# ATmega_2560_Pro.net
KiCad netlist of a schematic drawn in Altium Designer
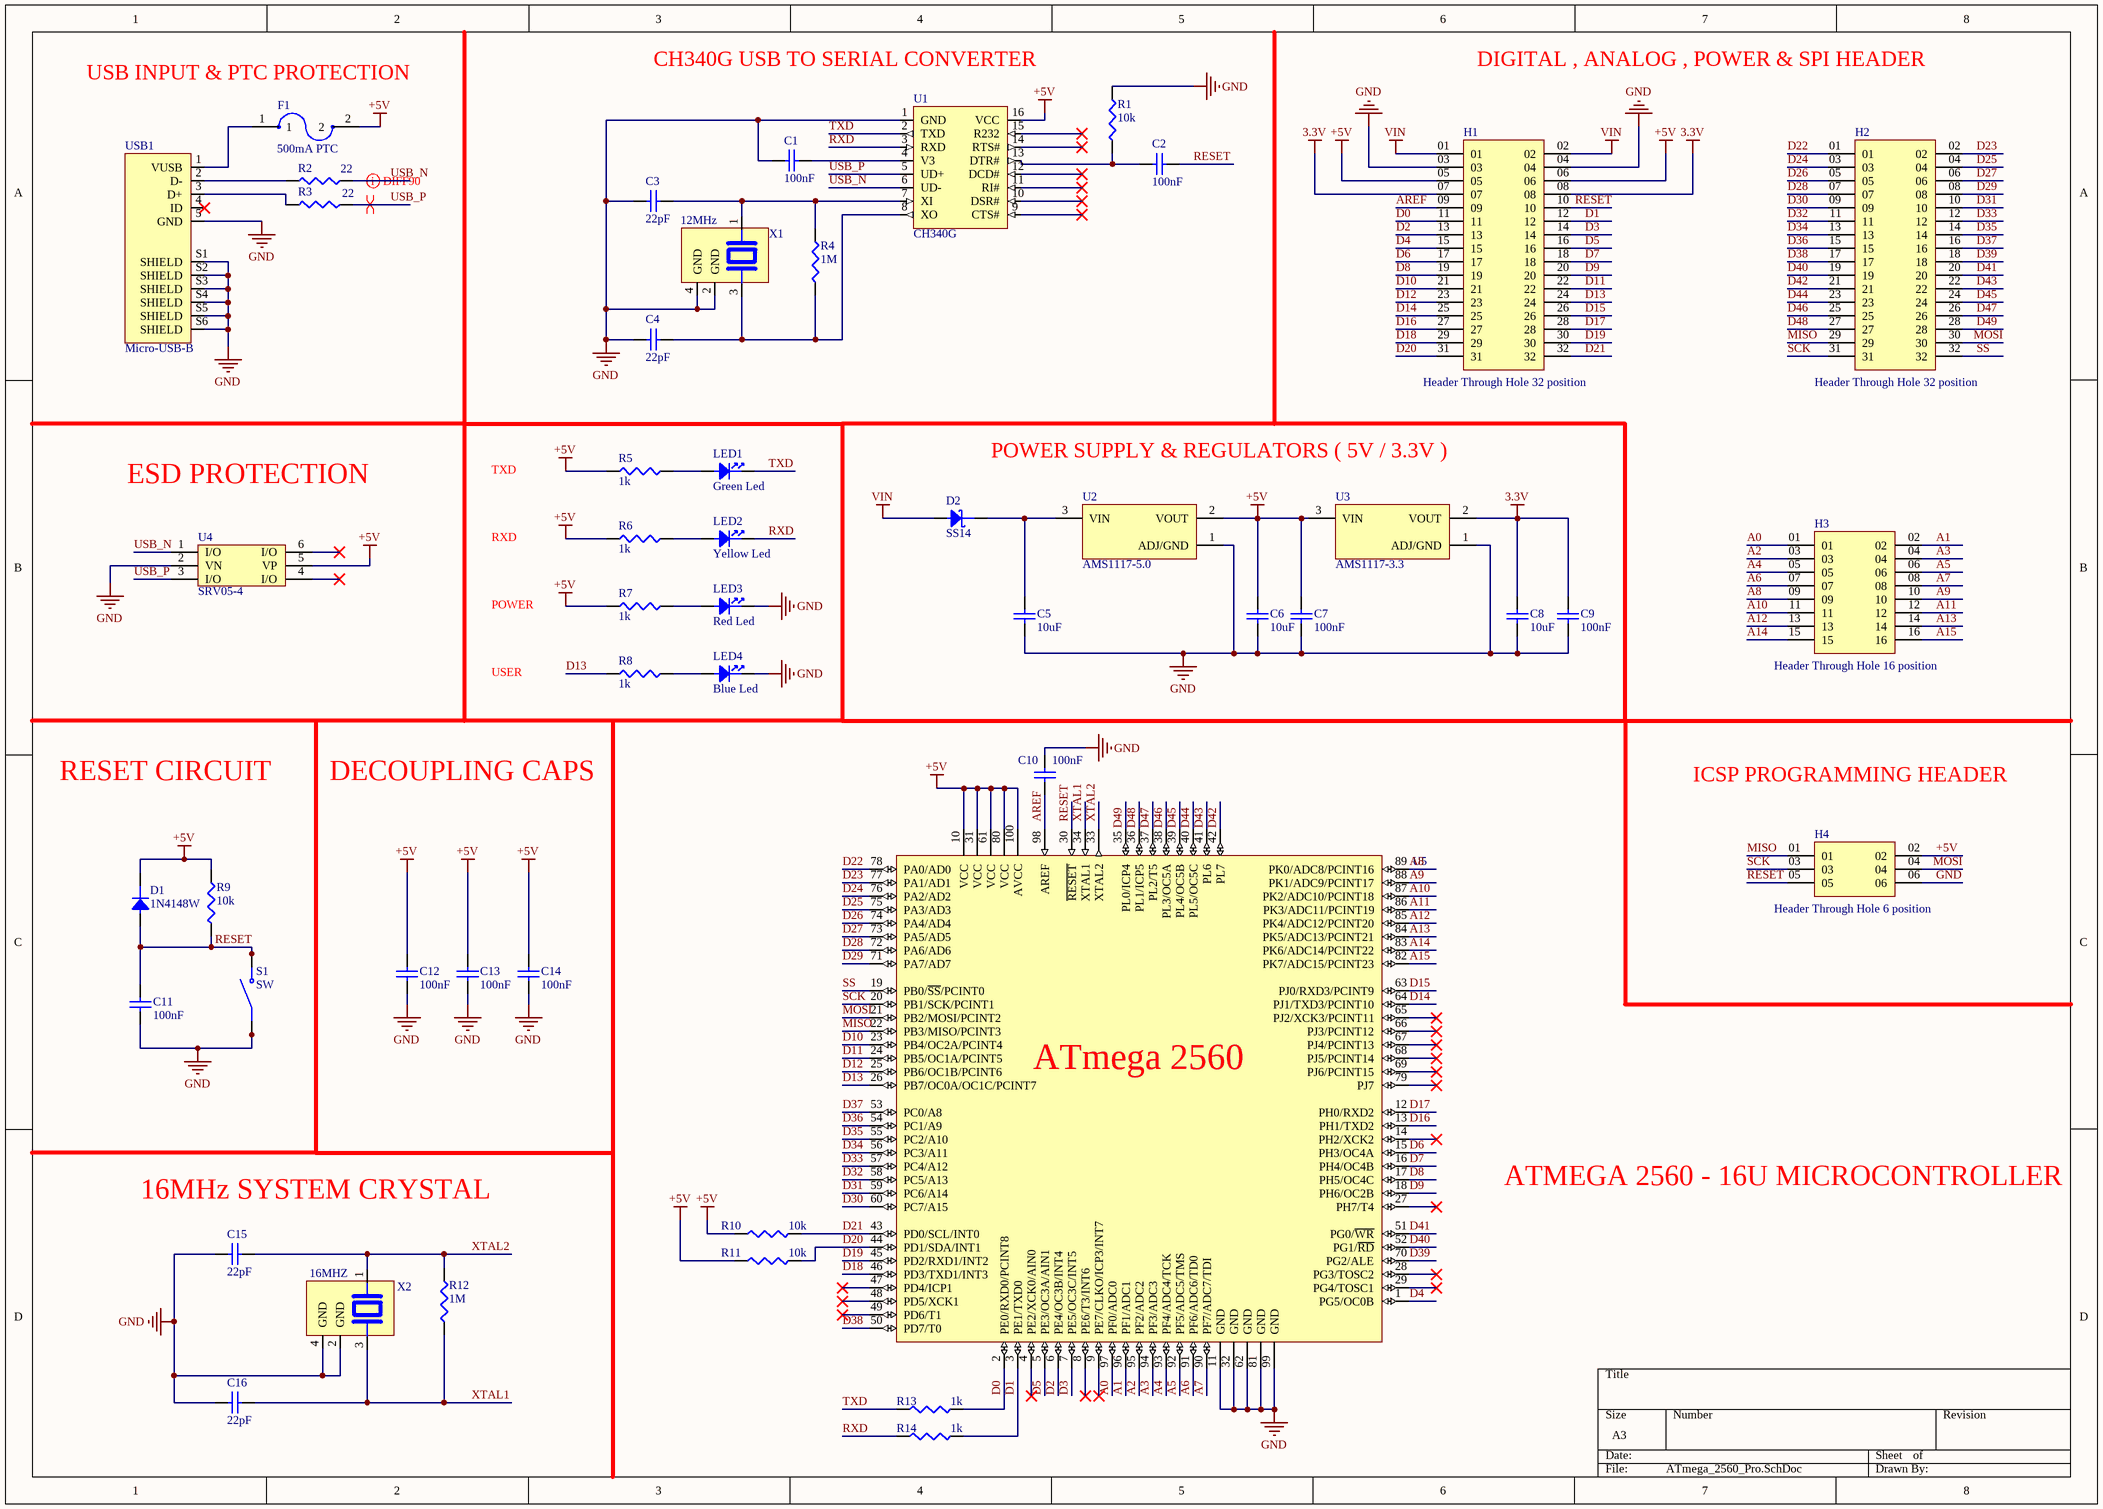
[diagram p0: ATmega_2560_Pro.SchDoc]

(export (version "E")
  (design (tool "Eeschema 10.0.6"))
  (components
    (comp (ref "C1")
      (value "100nF")
      (footprint "CAPC1608X90 - 100NF")
      (description "CAP CER 0.1UF 50V X7R 0603")
      (fields (field (name "TOLERANCE") "10%") (field (name "VOLTAGE") "50V"))
      (libsource (lib "Schlib") (part "CC0603KRX7R9BB104"))
    )
    (comp (ref "C2")
      (value "100nF")
      (footprint "CAPC1608X90 - 100NF")
      (description "CAP CER 0.1UF 50V X7R 0603")
      (fields (field (name "TOLERANCE") "10%") (field (name "VOLTAGE") "50V"))
      (libsource (lib "Schlib") (part "CC0603KRX7R9BB104"))
    )
    (comp (ref "C3")
      (value "22pF")
      (footprint "CAPC1608X90 - 22PF")
      (description "CAP CER 22PF 50V C0G/NPO 0603")
      (fields (field (name "TOLERANCE") "5%") (field (name "VOLTAGE") "50V"))
      (libsource (lib "Schlib") (part "CC0603JRNPO9BN220"))
    )
    (comp (ref "C4")
      (value "22pF")
      (footprint "CAPC1608X90 - 22PF")
      (description "CAP CER 22PF 50V C0G/NPO 0603")
      (fields (field (name "TOLERANCE") "5%") (field (name "VOLTAGE") "50V"))
      (libsource (lib "Schlib") (part "CC0603JRNPO9BN220"))
    )
    (comp (ref "C5")
      (value "10uF")
      (footprint "CAPC1608X90 - 10UF")
      (description "CAP CER 10UF 10V X5R 0603")
      (fields
        (field (name "MANUFACTURER") "Yageo Group")
        (field (name "MANUFACTURER PART NUMBER") "CC0603MRX5R6BB106")
      )
      (libsource (lib "Schlib") (part "CC0603MRX5R6BB106"))
    )
    (comp (ref "C6")
      (value "10uF")
      (footprint "CAPC1608X90 - 10UF")
      (description "CAP CER 10UF 10V X5R 0603")
      (fields
        (field (name "MANUFACTURER") "Yageo Group")
        (field (name "MANUFACTURER PART NUMBER") "CC0603MRX5R6BB106")
      )
      (libsource (lib "Schlib") (part "CC0603MRX5R6BB106"))
    )
    (comp (ref "C7")
      (value "100nF")
      (footprint "CAPC1608X90 - 100NF")
      (description "CAP CER 0.1UF 50V X7R 0603")
      (fields (field (name "TOLERANCE") "10%") (field (name "VOLTAGE") "50V"))
      (libsource (lib "Schlib") (part "CC0603KRX7R9BB104"))
    )
    (comp (ref "C8")
      (value "10uF")
      (footprint "CAPC1608X90 - 10UF")
      (description "CAP CER 10UF 10V X5R 0603")
      (fields
        (field (name "MANUFACTURER") "Yageo Group")
        (field (name "MANUFACTURER PART NUMBER") "CC0603MRX5R6BB106")
      )
      (libsource (lib "Schlib") (part "CC0603MRX5R6BB106"))
    )
    (comp (ref "C9")
      (value "100nF")
      (footprint "CAPC1608X90 - 100NF")
      (description "CAP CER 0.1UF 50V X7R 0603")
      (fields (field (name "TOLERANCE") "10%") (field (name "VOLTAGE") "50V"))
      (libsource (lib "Schlib") (part "CC0603KRX7R9BB104"))
    )
    (comp (ref "C10")
      (value "100nF")
      (footprint "CAPC1608X90 - 100NF")
      (description "CAP CER 0.1UF 50V X7R 0603")
      (fields (field (name "TOLERANCE") "10%") (field (name "VOLTAGE") "50V"))
      (libsource (lib "Schlib") (part "CC0603KRX7R9BB104"))
    )
    (comp (ref "C11")
      (value "100nF")
      (footprint "CAPC1608X90 - 100NF")
      (description "CAP CER 0.1UF 50V X7R 0603")
      (fields (field (name "TOLERANCE") "10%") (field (name "VOLTAGE") "50V"))
      (libsource (lib "Schlib") (part "CC0603KRX7R9BB104"))
    )
    (comp (ref "C12")
      (value "100nF")
      (footprint "CAPC1608X90 - 100NF")
      (description "CAP CER 0.1UF 50V X7R 0603")
      (fields (field (name "TOLERANCE") "10%") (field (name "VOLTAGE") "50V"))
      (libsource (lib "Schlib") (part "CC0603KRX7R9BB104"))
    )
    (comp (ref "C13")
      (value "100nF")
      (footprint "CAPC1608X90 - 100NF")
      (description "CAP CER 0.1UF 50V X7R 0603")
      (fields (field (name "TOLERANCE") "10%") (field (name "VOLTAGE") "50V"))
      (libsource (lib "Schlib") (part "CC0603KRX7R9BB104"))
    )
    (comp (ref "C14")
      (value "100nF")
      (footprint "CAPC1608X90 - 100NF")
      (description "CAP CER 0.1UF 50V X7R 0603")
      (fields (field (name "TOLERANCE") "10%") (field (name "VOLTAGE") "50V"))
      (libsource (lib "Schlib") (part "CC0603KRX7R9BB104"))
    )
    (comp (ref "C15")
      (value "22pF")
      (footprint "CAPC1608X90 - 22PF")
      (description "CAP CER 22PF 50V C0G/NPO 0603")
      (fields (field (name "TOLERANCE") "5%") (field (name "VOLTAGE") "50V"))
      (libsource (lib "Schlib") (part "CC0603JRNPO9BN220"))
    )
    (comp (ref "C16")
      (value "22pF")
      (footprint "CAPC1608X90 - 22PF")
      (description "CAP CER 22PF 50V C0G/NPO 0603")
      (fields (field (name "TOLERANCE") "5%") (field (name "VOLTAGE") "50V"))
      (libsource (lib "Schlib") (part "CC0603JRNPO9BN220"))
    )
    (comp (ref "D1")
      (value "1N4148W")
      (footprint "SOD123_DIO")
      (description "DIODE STANDARD 75V 250MA SOD123")
      (libsource (lib "Schlib") (part "1N4148W"))
    )
    (comp (ref "D2")
      (value "SS14")
      (footprint "DIOM4325X250N")
      (description "DIODE SCHOTTKY 40V 1A DO214AC")
      (fields (field (name "MANUFACTURER") "Taiwan Semiconductor"))
      (libsource (lib "Schlib") (part "SS14"))
    )
    (comp (ref "F1")
      (value "500mA PTC")
      (footprint "FUSM4632X85")
      (description "PTC RESET FUSE 15V 500MA 1812")
      (fields (field (name "MANUFACTURER") "Bourns") (field (name "MANUFACTURER PART NUMBER") "MF-MSMF050-2"))
      (libsource (lib "Schlib") (part "MF-MSMF050-2"))
    )
    (comp (ref "H1")
      (value "Header Through Hole 32 position")
      (footprint "SAMTEC_TSW-116-07-G-D")
      (description "Connector Header Through Hole 32 position 0.100\" (2.54mm)")
      (fields
        (field (name "MANUFACTURER") "Samtec")
        (field (name "MANUFACTURER PART NUMBER") "TSW-116-07-G-D")
      )
      (libsource (lib "Schlib") (part "TSW-116-07-G-D"))
    )
    (comp (ref "H2")
      (value "Header Through Hole 32 position")
      (footprint "SAMTEC_TSW-116-07-G-D")
      (description "Connector Header Through Hole 32 position 0.100\" (2.54mm)")
      (fields
        (field (name "MANUFACTURER") "Samtec")
        (field (name "MANUFACTURER PART NUMBER") "TSW-116-07-G-D")
      )
      (libsource (lib "Schlib") (part "TSW-116-07-G-D"))
    )
    (comp (ref "H3")
      (value "Header Through Hole 16 position")
      (footprint "SAMTEC_TSW-108-07-G-D")
      (description "Connector Header Through Hole 16 position 0.100\" (2.54mm)")
      (fields
        (field (name "MANUFACTURER") "Samtec")
        (field (name "MANUFACTURER PART NUMBER") "TSW-108-07-G-D")
      )
      (libsource (lib "Schlib") (part "TSW-108-07-G-D"))
    )
    (comp (ref "H4")
      (value "Header Through Hole 6 position")
      (footprint "SAMTEC_TSW-103-07-G-D")
      (description "CONN HEADER VERT 6POS 2.54MM")
      (fields
        (field (name "MANUFACTURER") "Samtec")
        (field (name "MANUFACTURER PART NUMBER") "TSW-103-07-G-D")
      )
      (libsource (lib "Schlib") (part "TSW-103-07-G-D"))
    )
    (comp (ref "LED1")
      (value "Green Led")
      (footprint "WL-SMCW_0603-G")
      (description "LED GREEN CLEAR 0603 SMD")
      (fields
        (field (name "MANUFACTURER") "Wurth Elektronik")
        (field (name "MANUFACTURER PART NUMBER") "150060VS75000")
      )
      (libsource (lib "Schlib") (part "150060VS75000"))
    )
    (comp (ref "LED2")
      (value "Yellow Led")
      (footprint "WL-SMCW_0603-Y")
      (description "LED YELLOW CLEAR 0603 SMD")
      (fields
        (field (name "MANUFACTURER") "Wurth Elektronik")
        (field (name "MANUFACTURER PART NUMBER") "150060YS75000")
      )
      (libsource (lib "Schlib") (part "150060YS75000"))
    )
    (comp (ref "LED3")
      (value "Red Led")
      (footprint "WL-SMCW_0603-R")
      (description "LED RED CLEAR 0603 SMD")
      (fields
        (field (name "MANUFACTURER") "Wurth Elektronik")
        (field (name "MANUFACTURER PART NUMBER") "150060RS75000")
      )
      (libsource (lib "Schlib") (part "150060RS75000"))
    )
    (comp (ref "LED4")
      (value "Blue Led")
      (footprint "WL-SMCW_0603-B")
      (description "LED BLUE CLEAR 0603 SMD")
      (fields
        (field (name "MANUFACTURER") "Wurth Elektronik")
        (field (name "MANUFACTURER PART NUMBER") "150060BS75000")
      )
      (libsource (lib "Schlib") (part "150060BS75000"))
    )
    (comp (ref "R1")
      (value "10k")
      (footprint "RESC1607X60N - 10K")
      (description "RES 10K OHM 1% 1/10W 0603")
      (fields (field (name "TOLERANCE") "1%"))
      (libsource (lib "Schlib") (part "RC0603FR-0710KL"))
    )
    (comp (ref "R2")
      (value "22")
      (footprint "RESC1607X60N - 22")
      (description "RES 22 OHM 1% 1/10W 0603")
      (fields
        (field (name "MANUFACTURER") "Yageo Group")
        (field (name "MANUFACTURER PART NUMBER") "RC0603FR-0722RL")
      )
      (libsource (lib "Schlib") (part "RC0603FR-0722RL"))
    )
    (comp (ref "R3")
      (value "22")
      (footprint "RESC1607X60N - 22")
      (description "RES 22 OHM 1% 1/10W 0603")
      (fields
        (field (name "MANUFACTURER") "Yageo Group")
        (field (name "MANUFACTURER PART NUMBER") "RC0603FR-0722RL")
      )
      (libsource (lib "Schlib") (part "RC0603FR-0722RL"))
    )
    (comp (ref "R4")
      (value "1M")
      (footprint "RESC1607X60N - 1M")
      (description "RES 1M OHM 1% 1/10W 0603")
      (fields (field (name "TOLERANCE") "1%"))
      (libsource (lib "Schlib") (part "RC0603FR-071ML"))
    )
    (comp (ref "R5")
      (value "1k")
      (footprint "RESC1607X60N - 1K")
      (description "RES 1K OHM 1% 1/10W 0603")
      (fields (field (name "TOLERANCE") "1%"))
      (libsource (lib "Schlib") (part "RC0603FR-071KL"))
    )
    (comp (ref "R6")
      (value "1k")
      (footprint "RESC1607X60N - 1K")
      (description "RES 1K OHM 1% 1/10W 0603")
      (fields (field (name "TOLERANCE") "1%"))
      (libsource (lib "Schlib") (part "RC0603FR-071KL"))
    )
    (comp (ref "R7")
      (value "1k")
      (footprint "RESC1607X60N - 1K")
      (description "RES 1K OHM 1% 1/10W 0603")
      (fields (field (name "TOLERANCE") "1%"))
      (libsource (lib "Schlib") (part "RC0603FR-071KL"))
    )
    (comp (ref "R8")
      (value "1k")
      (footprint "RESC1607X60N - 1K")
      (description "RES 1K OHM 1% 1/10W 0603")
      (fields (field (name "TOLERANCE") "1%"))
      (libsource (lib "Schlib") (part "RC0603FR-071KL"))
    )
    (comp (ref "R9")
      (value "10k")
      (footprint "RESC1607X60N - 10K")
      (description "RES 10K OHM 1% 1/10W 0603")
      (fields (field (name "TOLERANCE") "1%"))
      (libsource (lib "Schlib") (part "RC0603FR-0710KL"))
    )
    (comp (ref "R10")
      (value "10k")
      (footprint "RESC1607X60N - 10K")
      (description "RES 10K OHM 1% 1/10W 0603")
      (fields (field (name "TOLERANCE") "1%"))
      (libsource (lib "Schlib") (part "RC0603FR-0710KL"))
    )
    (comp (ref "R11")
      (value "10k")
      (footprint "RESC1607X60N - 10K")
      (description "RES 10K OHM 1% 1/10W 0603")
      (fields (field (name "TOLERANCE") "1%"))
      (libsource (lib "Schlib") (part "RC0603FR-0710KL"))
    )
    (comp (ref "R12")
      (value "1M")
      (footprint "RESC1607X60N - 1M")
      (description "RES 1M OHM 1% 1/10W 0603")
      (fields (field (name "TOLERANCE") "1%"))
      (libsource (lib "Schlib") (part "RC0603FR-071ML"))
    )
    (comp (ref "R13")
      (value "1k")
      (footprint "RESC1607X60N - 1K")
      (description "RES 1K OHM 1% 1/10W 0603")
      (fields (field (name "TOLERANCE") "1%"))
      (libsource (lib "Schlib") (part "RC0603FR-071KL"))
    )
    (comp (ref "R14")
      (value "1k")
      (footprint "RESC1607X60N - 1K")
      (description "RES 1K OHM 1% 1/10W 0603")
      (fields (field (name "TOLERANCE") "1%"))
      (libsource (lib "Schlib") (part "RC0603FR-071KL"))
    )
    (comp (ref "S1")
      (value "SW")
      (footprint "SW_TS-1187A-B-A-B")
      (description "SWITCH TACTILE SPST-NO 0.05A 12V SMD 3X4MM")
      (libsource (lib "Schlib") (part "TS-1187A-B-A-B"))
    )
    (comp (ref "U1")
      (value "CH340G")
      (footprint "SOP127P780X200-16N")
      (description "USB to Serial UART Interface Controller IC, SOP-16, 5V/3.3V, 12MHz External Crystal Required")
      (libsource (lib "Schlib") (part "CH340G"))
    )
    (comp (ref "U2")
      (value "AMS1117-5.0")
      (footprint "SOT229P700X180-4N-5.0")
      (description "IC REG LINEAR 5.1V 1A SOT-223-3L")
      (fields (field (name "MANUFACTURER") "Revvo"))
      (libsource (lib "Schlib") (part "AMS1117-5.0"))
    )
    (comp (ref "U3")
      (value "AMS1117-3.3")
      (footprint "SOT229P700X180-4N-3.3")
      (description "IC REG LINEAR 3.3V 1A SOT-223-3L")
      (fields (field (name "MANUFACTURER") "UMW(Youtai Semiconductor Co., Ltd.)"))
      (libsource (lib "Schlib") (part "AMS1117-3.3"))
    )
    (comp (ref "U4")
      (value "SRV05-4")
      (footprint "TSOP6_3P1X1P7_ONS")
      (description "TVS DIODE 5VWM 17.5VC 6TSOP")
      (fields
        (field (name "MANUFACTURER") "onsemi")
        (field (name "MANUFACTURER PART NUMBER") "SRV05-4MR6T1G")
      )
      (libsource (lib "Schlib") (part "SRV05-4MR6T1G"))
    )
    (comp (ref "U5")
      (value "ATMEGA2560-16AU")
      (footprint "QFP50P1600X1600X120-100N")
      (description "IC MCU 8BIT 256KB FLASH 100TQFP")
      (fields (field (name "MANUFACTURER") "Microchip"))
      (libsource (lib "Schlib") (part "ATMEGA2560-16AU"))
    )
    (comp (ref "USB1")
      (value "Micro-USB-B")
      (footprint "AMPHENOL_10118193-0001LF")
      (description "CONN RCPT USB2.0 MICRO B SMD R/A")
      (fields
        (field (name "MANUFACTURER") "Amphenol Communications Solutions")
        (field (name "MANUFACTURER PART NUMBER") "10118193-0001LF")
      )
      (libsource (lib "Schlib") (part "10118193-0001LF"))
    )
    (comp (ref "X1")
      (value "12MHz")
      (footprint "OSCCC250X320X70-4N")
      (description "CRYSTAL 12.0000MHZ 18PF SMD")
      (fields (field (name "TOLERANCE") "0.003%"))
      (libsource (lib "Schlib") (part "7M-12.000MAAJ-T"))
    )
    (comp (ref "X2")
      (value "16MHZ")
      (footprint "XTAL_7M-16.000MAAJ-T")
      (description "CRYSTAL 16.0000MHZ 18PF SMD")
      (fields (field (name "TOLERANCE") "0.003%"))
      (libsource (lib "Schlib") (part "7M-16.000MAAJ-T"))
    )
  )
  (nets
    (net (code "1") (name "+5V") (class "Default")
      (node (ref "C12") (pin "2") (pinfunction "2_2") (pintype "passive"))
      (node (ref "C13") (pin "2") (pinfunction "2_2") (pintype "passive"))
      (node (ref "C14") (pin "2") (pinfunction "2_2") (pintype "passive"))
      (node (ref "C6") (pin "2") (pinfunction "2_2") (pintype "passive"))
      (node (ref "C7") (pin "2") (pinfunction "2_2") (pintype "passive"))
      (node (ref "D1") (pin "1") (pinfunction "1_1") (pintype "passive"))
      (node (ref "F1") (pin "2") (pinfunction "2_2") (pintype "passive"))
      (node (ref "H1") (pin "05") (pinfunction "05_05") (pintype "power_in"))
      (node (ref "H1") (pin "06") (pinfunction "06_06") (pintype "power_in"))
      (node (ref "H4") (pin "02") (pinfunction "02_02") (pintype "passive"))
      (node (ref "R10") (pin "2") (pinfunction "2_2") (pintype "passive"))
      (node (ref "R11") (pin "2") (pinfunction "2_2") (pintype "passive"))
      (node (ref "R5") (pin "1") (pinfunction "1_1") (pintype "passive"))
      (node (ref "R6") (pin "1") (pinfunction "1_1") (pintype "passive"))
      (node (ref "R7") (pin "1") (pinfunction "1_1") (pintype "passive"))
      (node (ref "R9") (pin "2") (pinfunction "2_2") (pintype "passive"))
      (node (ref "U1") (pin "16") (pinfunction "VCC_16") (pintype "power_in"))
      (node (ref "U2") (pin "2") (pinfunction "VOUT_2") (pintype "power_in"))
      (node (ref "U3") (pin "3") (pinfunction "VIN_3") (pintype "power_in"))
      (node (ref "U4") (pin "5") (pinfunction "VP_5") (pintype "power_in"))
      (node (ref "U5") (pin "10") (pinfunction "VCC_10") (pintype "power_in"))
      (node (ref "U5") (pin "100") (pinfunction "AVCC_100") (pintype "power_in"))
      (node (ref "U5") (pin "31") (pinfunction "VCC_31") (pintype "power_in"))
      (node (ref "U5") (pin "61") (pinfunction "VCC_61") (pintype "power_in"))
      (node (ref "U5") (pin "80") (pinfunction "VCC_80") (pintype "power_in"))
    )
    (net (code "2") (name "/A0") (class "Default")
      (node (ref "H3") (pin "01") (pinfunction "01_01") (pintype "passive"))
      (node (ref "U5") (pin "97") (pinfunction "PF0/ADC0_97") (pintype "bidirectional"))
    )
    (net (code "3") (name "/A1") (class "Default")
      (node (ref "H3") (pin "02") (pinfunction "02_02") (pintype "passive"))
      (node (ref "U5") (pin "96") (pinfunction "PF1/ADC1_96") (pintype "bidirectional"))
    )
    (net (code "4") (name "/A2") (class "Default")
      (node (ref "H3") (pin "03") (pinfunction "03_03") (pintype "passive"))
      (node (ref "U5") (pin "95") (pinfunction "PF2/ADC2_95") (pintype "bidirectional"))
    )
    (net (code "5") (name "/A3") (class "Default")
      (node (ref "H3") (pin "04") (pinfunction "04_04") (pintype "passive"))
      (node (ref "U5") (pin "94") (pinfunction "PF3/ADC3_94") (pintype "bidirectional"))
    )
    (net (code "6") (name "/A4") (class "Default")
      (node (ref "H3") (pin "05") (pinfunction "05_05") (pintype "passive"))
      (node (ref "U5") (pin "93") (pinfunction "PF4/ADC4/TCK_93") (pintype "bidirectional"))
    )
    (net (code "7") (name "/A5") (class "Default")
      (node (ref "H3") (pin "06") (pinfunction "06_06") (pintype "passive"))
      (node (ref "U5") (pin "92") (pinfunction "PF5/ADC5/TMS_92") (pintype "bidirectional"))
    )
    (net (code "8") (name "/A6") (class "Default")
      (node (ref "H3") (pin "07") (pinfunction "07_07") (pintype "passive"))
      (node (ref "U5") (pin "91") (pinfunction "PF6/ADC6/TD0_91") (pintype "bidirectional"))
    )
    (net (code "9") (name "/A7") (class "Default")
      (node (ref "H3") (pin "08") (pinfunction "08_08") (pintype "passive"))
      (node (ref "U5") (pin "90") (pinfunction "PF7/ADC7/TDI_90") (pintype "bidirectional"))
    )
    (net (code "10") (name "/A8") (class "Default")
      (node (ref "H3") (pin "09") (pinfunction "09_09") (pintype "passive"))
      (node (ref "U5") (pin "89") (pinfunction "PK0/ADC8/PCINT16_89") (pintype "bidirectional"))
    )
    (net (code "11") (name "/A9") (class "Default")
      (node (ref "H3") (pin "10") (pinfunction "10_10") (pintype "passive"))
      (node (ref "U5") (pin "88") (pinfunction "PK1/ADC9/PCINT17_88") (pintype "bidirectional"))
    )
    (net (code "12") (name "/A10") (class "Default")
      (node (ref "H3") (pin "11") (pinfunction "11_11") (pintype "passive"))
      (node (ref "U5") (pin "87") (pinfunction "PK2/ADC10/PCINT18_87") (pintype "bidirectional"))
    )
    (net (code "13") (name "/A11") (class "Default")
      (node (ref "H3") (pin "12") (pinfunction "12_12") (pintype "passive"))
      (node (ref "U5") (pin "86") (pinfunction "PK3/ADC11/PCINT19_86") (pintype "bidirectional"))
    )
    (net (code "14") (name "/A12") (class "Default")
      (node (ref "H3") (pin "13") (pinfunction "13_13") (pintype "passive"))
      (node (ref "U5") (pin "85") (pinfunction "PK4/ADC12/PCINT20_85") (pintype "bidirectional"))
    )
    (net (code "15") (name "/A13") (class "Default")
      (node (ref "H3") (pin "14") (pinfunction "14_14") (pintype "passive"))
      (node (ref "U5") (pin "84") (pinfunction "PK5/ADC13/PCINT21_84") (pintype "bidirectional"))
    )
    (net (code "16") (name "/A14") (class "Default")
      (node (ref "H3") (pin "15") (pinfunction "15_15") (pintype "passive"))
      (node (ref "U5") (pin "83") (pinfunction "PK6/ADC14/PCINT22_83") (pintype "bidirectional"))
    )
    (net (code "17") (name "/A15") (class "Default")
      (node (ref "H3") (pin "16") (pinfunction "16_16") (pintype "passive"))
      (node (ref "U5") (pin "82") (pinfunction "PK7/ADC15/PCINT23_82") (pintype "bidirectional"))
    )
    (net (code "18") (name "/AREF") (class "Default")
      (node (ref "C10") (pin "1") (pinfunction "1_1") (pintype "passive"))
      (node (ref "H1") (pin "09") (pinfunction "09_09") (pintype "passive"))
      (node (ref "U5") (pin "98") (pinfunction "AREF_98") (pintype "input"))
    )
    (net (code "19") (name "/D0") (class "Default")
      (node (ref "H1") (pin "11") (pinfunction "11_11") (pintype "passive"))
      (node (ref "R13") (pin "2") (pinfunction "2_2") (pintype "passive"))
      (node (ref "U5") (pin "2") (pinfunction "PE0/RXD0/PCINT8_2") (pintype "bidirectional"))
    )
    (net (code "20") (name "/D1") (class "Default")
      (node (ref "H1") (pin "12") (pinfunction "12_12") (pintype "passive"))
      (node (ref "R14") (pin "2") (pinfunction "2_2") (pintype "passive"))
      (node (ref "U5") (pin "3") (pinfunction "PE1/TXD0_3") (pintype "bidirectional"))
    )
    (net (code "21") (name "/D2") (class "Default")
      (node (ref "H1") (pin "13") (pinfunction "13_13") (pintype "passive"))
      (node (ref "U5") (pin "6") (pinfunction "PE4/OC3B/INT4_6") (pintype "bidirectional"))
    )
    (net (code "22") (name "/D3") (class "Default")
      (node (ref "H1") (pin "14") (pinfunction "14_14") (pintype "passive"))
      (node (ref "U5") (pin "7") (pinfunction "PE5/OC3C/INT5_7") (pintype "bidirectional"))
    )
    (net (code "23") (name "/D4") (class "Default")
      (node (ref "H1") (pin "15") (pinfunction "15_15") (pintype "passive"))
      (node (ref "U5") (pin "1") (pinfunction "_PG5/OC0B_1") (pintype "bidirectional"))
    )
    (net (code "24") (name "/D5") (class "Default")
      (node (ref "H1") (pin "16") (pinfunction "16_16") (pintype "passive"))
      (node (ref "U5") (pin "5") (pinfunction "PE3/OC3A/AIN1_5") (pintype "bidirectional"))
    )
    (net (code "25") (name "/D6") (class "Default")
      (node (ref "H1") (pin "17") (pinfunction "17_17") (pintype "passive"))
      (node (ref "U5") (pin "15") (pinfunction "PH3/OC4A_15") (pintype "bidirectional"))
    )
    (net (code "26") (name "/D7") (class "Default")
      (node (ref "H1") (pin "18") (pinfunction "18_18") (pintype "passive"))
      (node (ref "U5") (pin "16") (pinfunction "PH4/OC4B_16") (pintype "bidirectional"))
    )
    (net (code "27") (name "/D8") (class "Default")
      (node (ref "H1") (pin "19") (pinfunction "19_19") (pintype "passive"))
      (node (ref "U5") (pin "17") (pinfunction "PH5/OC4C_17") (pintype "bidirectional"))
    )
    (net (code "28") (name "/D9") (class "Default")
      (node (ref "H1") (pin "20") (pinfunction "20_20") (pintype "passive"))
      (node (ref "U5") (pin "18") (pinfunction "PH6/OC2B_18") (pintype "bidirectional"))
    )
    (net (code "29") (name "/D10") (class "Default")
      (node (ref "H1") (pin "21") (pinfunction "21_21") (pintype "passive"))
      (node (ref "U5") (pin "23") (pinfunction "PB4/OC2A/PCINT4_23") (pintype "bidirectional"))
    )
    (net (code "30") (name "/D11") (class "Default")
      (node (ref "H1") (pin "22") (pinfunction "22_22") (pintype "passive"))
      (node (ref "U5") (pin "24") (pinfunction "PB5/OC1A/PCINT5_24") (pintype "bidirectional"))
    )
    (net (code "31") (name "/D12") (class "Default")
      (node (ref "H1") (pin "23") (pinfunction "23_23") (pintype "passive"))
      (node (ref "U5") (pin "25") (pinfunction "PB6/OC1B/PCINT6_25") (pintype "bidirectional"))
    )
    (net (code "32") (name "/D13") (class "Default")
      (node (ref "H1") (pin "24") (pinfunction "24_24") (pintype "passive"))
      (node (ref "R8") (pin "1") (pinfunction "1_1") (pintype "passive"))
      (node (ref "U5") (pin "26") (pinfunction "PB7/OC0A/OC1C/PCINT7_26") (pintype "bidirectional"))
    )
    (net (code "33") (name "/D14") (class "Default")
      (node (ref "H1") (pin "25") (pinfunction "25_25") (pintype "passive"))
      (node (ref "U5") (pin "64") (pinfunction "PJ1/TXD3/PCINT10_64") (pintype "bidirectional"))
    )
    (net (code "34") (name "/D15") (class "Default")
      (node (ref "H1") (pin "26") (pinfunction "26_26") (pintype "passive"))
      (node (ref "U5") (pin "63") (pinfunction "PJ0/RXD3/PCINT9_63") (pintype "bidirectional"))
    )
    (net (code "35") (name "/D16") (class "Default")
      (node (ref "H1") (pin "27") (pinfunction "27_27") (pintype "passive"))
      (node (ref "U5") (pin "13") (pinfunction "PH1/TXD2_13") (pintype "bidirectional"))
    )
    (net (code "36") (name "/D17") (class "Default")
      (node (ref "H1") (pin "28") (pinfunction "28_28") (pintype "passive"))
      (node (ref "U5") (pin "12") (pinfunction "PH0/RXD2_12") (pintype "bidirectional"))
    )
    (net (code "37") (name "/D18") (class "Default")
      (node (ref "H1") (pin "29") (pinfunction "29_29") (pintype "passive"))
      (node (ref "U5") (pin "46") (pinfunction "PD3/TXD1/INT3_46") (pintype "bidirectional"))
    )
    (net (code "38") (name "/D19") (class "Default")
      (node (ref "H1") (pin "30") (pinfunction "30_30") (pintype "passive"))
      (node (ref "U5") (pin "45") (pinfunction "PD2/RXD1/INT2_45") (pintype "bidirectional"))
    )
    (net (code "39") (name "/D20") (class "Default")
      (node (ref "H1") (pin "31") (pinfunction "31_31") (pintype "passive"))
      (node (ref "R11") (pin "1") (pinfunction "1_1") (pintype "passive"))
      (node (ref "U5") (pin "44") (pinfunction "PD1/SDA/INT1_44") (pintype "bidirectional"))
    )
    (net (code "40") (name "/D21") (class "Default")
      (node (ref "H1") (pin "32") (pinfunction "32_32") (pintype "passive"))
      (node (ref "R10") (pin "1") (pinfunction "1_1") (pintype "passive"))
      (node (ref "U5") (pin "43") (pinfunction "PD0/SCL/INT0_43") (pintype "bidirectional"))
    )
    (net (code "41") (name "/D22") (class "Default")
      (node (ref "H2") (pin "01") (pinfunction "01_01") (pintype "power_in"))
      (node (ref "U5") (pin "78") (pinfunction "PA0/AD0_78") (pintype "bidirectional"))
    )
    (net (code "42") (name "/D23") (class "Default")
      (node (ref "H2") (pin "02") (pinfunction "02_02") (pintype "power_in"))
      (node (ref "U5") (pin "77") (pinfunction "PA1/AD1_77") (pintype "bidirectional"))
    )
    (net (code "43") (name "/D24") (class "Default")
      (node (ref "H2") (pin "03") (pinfunction "03_03") (pintype "power_in"))
      (node (ref "U5") (pin "76") (pinfunction "PA2/AD2_76") (pintype "bidirectional"))
    )
    (net (code "44") (name "/D25") (class "Default")
      (node (ref "H2") (pin "04") (pinfunction "04_04") (pintype "power_in"))
      (node (ref "U5") (pin "75") (pinfunction "PA3/AD3_75") (pintype "bidirectional"))
    )
    (net (code "45") (name "/D26") (class "Default")
      (node (ref "H2") (pin "05") (pinfunction "05_05") (pintype "power_in"))
      (node (ref "U5") (pin "74") (pinfunction "PA4/AD4_74") (pintype "bidirectional"))
    )
    (net (code "46") (name "/D27") (class "Default")
      (node (ref "H2") (pin "06") (pinfunction "06_06") (pintype "power_in"))
      (node (ref "U5") (pin "73") (pinfunction "PA5/AD5_73") (pintype "bidirectional"))
    )
    (net (code "47") (name "/D28") (class "Default")
      (node (ref "H2") (pin "07") (pinfunction "07_07") (pintype "power_in"))
      (node (ref "U5") (pin "72") (pinfunction "PA6/AD6_72") (pintype "bidirectional"))
    )
    (net (code "48") (name "/D29") (class "Default")
      (node (ref "H2") (pin "08") (pinfunction "08_08") (pintype "power_in"))
      (node (ref "U5") (pin "71") (pinfunction "PA7/AD7_71") (pintype "bidirectional"))
    )
    (net (code "49") (name "/D30") (class "Default")
      (node (ref "H2") (pin "09") (pinfunction "09_09") (pintype "passive"))
      (node (ref "U5") (pin "60") (pinfunction "PC7/A15_60") (pintype "bidirectional"))
    )
    (net (code "50") (name "/D31") (class "Default")
      (node (ref "H2") (pin "10") (pinfunction "10_10") (pintype "passive"))
      (node (ref "U5") (pin "59") (pinfunction "PC6/A14_59") (pintype "bidirectional"))
    )
    (net (code "51") (name "/D32") (class "Default")
      (node (ref "H2") (pin "11") (pinfunction "11_11") (pintype "passive"))
      (node (ref "U5") (pin "58") (pinfunction "PC5/A13_58") (pintype "bidirectional"))
    )
    (net (code "52") (name "/D33") (class "Default")
      (node (ref "H2") (pin "12") (pinfunction "12_12") (pintype "passive"))
      (node (ref "U5") (pin "57") (pinfunction "PC4/A12_57") (pintype "bidirectional"))
    )
    (net (code "53") (name "/D34") (class "Default")
      (node (ref "H2") (pin "13") (pinfunction "13_13") (pintype "passive"))
      (node (ref "U5") (pin "56") (pinfunction "PC3/A11_56") (pintype "bidirectional"))
    )
    (net (code "54") (name "/D35") (class "Default")
      (node (ref "H2") (pin "14") (pinfunction "14_14") (pintype "passive"))
      (node (ref "U5") (pin "55") (pinfunction "PC2/A10_55") (pintype "bidirectional"))
    )
    (net (code "55") (name "/D36") (class "Default")
      (node (ref "H2") (pin "15") (pinfunction "15_15") (pintype "passive"))
      (node (ref "U5") (pin "54") (pinfunction "PC1/A9_54") (pintype "bidirectional"))
    )
    (net (code "56") (name "/D37") (class "Default")
      (node (ref "H2") (pin "16") (pinfunction "16_16") (pintype "passive"))
      (node (ref "U5") (pin "53") (pinfunction "PC0/A8_53") (pintype "bidirectional"))
    )
    (net (code "57") (name "/D38") (class "Default")
      (node (ref "H2") (pin "17") (pinfunction "17_17") (pintype "passive"))
      (node (ref "U5") (pin "50") (pinfunction "PD7/T0_50") (pintype "bidirectional"))
    )
    (net (code "58") (name "/D39") (class "Default")
      (node (ref "H2") (pin "18") (pinfunction "18_18") (pintype "passive"))
      (node (ref "U5") (pin "70") (pinfunction "PG2/ALE_70") (pintype "bidirectional"))
    )
    (net (code "59") (name "/D40") (class "Default")
      (node (ref "H2") (pin "19") (pinfunction "19_19") (pintype "passive"))
      (node (ref "U5") (pin "52") (pinfunction "PG1/~{RD}_52") (pintype "bidirectional"))
    )
    (net (code "60") (name "/D41") (class "Default")
      (node (ref "H2") (pin "20") (pinfunction "20_20") (pintype "passive"))
      (node (ref "U5") (pin "51") (pinfunction "PG0/~{WR}_51") (pintype "bidirectional"))
    )
    (net (code "61") (name "/D42") (class "Default")
      (node (ref "H2") (pin "21") (pinfunction "21_21") (pintype "passive"))
      (node (ref "U5") (pin "42") (pinfunction "PL7_42") (pintype "bidirectional"))
    )
    (net (code "62") (name "/D43") (class "Default")
      (node (ref "H2") (pin "22") (pinfunction "22_22") (pintype "passive"))
      (node (ref "U5") (pin "41") (pinfunction "PL6_41") (pintype "bidirectional"))
    )
    (net (code "63") (name "/D44") (class "Default")
      (node (ref "H2") (pin "23") (pinfunction "23_23") (pintype "passive"))
      (node (ref "U5") (pin "40") (pinfunction "PL5/OC5C_40") (pintype "bidirectional"))
    )
    (net (code "64") (name "/D45") (class "Default")
      (node (ref "H2") (pin "24") (pinfunction "24_24") (pintype "passive"))
      (node (ref "U5") (pin "39") (pinfunction "PL4/OC5B_39") (pintype "bidirectional"))
    )
    (net (code "65") (name "/D46") (class "Default")
      (node (ref "H2") (pin "25") (pinfunction "25_25") (pintype "passive"))
      (node (ref "U5") (pin "38") (pinfunction "PL3/OC5A_38") (pintype "bidirectional"))
    )
    (net (code "66") (name "/D47") (class "Default")
      (node (ref "H2") (pin "26") (pinfunction "26_26") (pintype "passive"))
      (node (ref "U5") (pin "37") (pinfunction "PL2/T5_37") (pintype "bidirectional"))
    )
    (net (code "67") (name "/D48") (class "Default")
      (node (ref "H2") (pin "27") (pinfunction "27_27") (pintype "passive"))
      (node (ref "U5") (pin "36") (pinfunction "PL1/ICP5_36") (pintype "bidirectional"))
    )
    (net (code "68") (name "/D49") (class "Default")
      (node (ref "H2") (pin "28") (pinfunction "28_28") (pintype "passive"))
      (node (ref "U5") (pin "35") (pinfunction "PL0/ICP4_35") (pintype "bidirectional"))
    )
    (net (code "69") (name "/MISO") (class "Default")
      (node (ref "H2") (pin "29") (pinfunction "29_29") (pintype "passive"))
      (node (ref "H4") (pin "01") (pinfunction "01_01") (pintype "passive"))
      (node (ref "U5") (pin "22") (pinfunction "PB3/MISO/PCINT3_22") (pintype "bidirectional"))
    )
    (net (code "70") (name "/MOSI") (class "Default")
      (node (ref "H2") (pin "30") (pinfunction "30_30") (pintype "passive"))
      (node (ref "H4") (pin "04") (pinfunction "04_04") (pintype "passive"))
      (node (ref "U5") (pin "21") (pinfunction "PB2/MOSI/PCINT2_21") (pintype "bidirectional"))
    )
    (net (code "71") (name "/RESET") (class "Default")
      (node (ref "C11") (pin "2") (pinfunction "2_2") (pintype "passive"))
      (node (ref "C2") (pin "2") (pinfunction "2_2") (pintype "passive"))
      (node (ref "D1") (pin "2") (pinfunction "2_2") (pintype "passive"))
      (node (ref "H1") (pin "10") (pinfunction "10_10") (pintype "passive"))
      (node (ref "H4") (pin "05") (pinfunction "05_05") (pintype "passive"))
      (node (ref "R9") (pin "1") (pinfunction "1_1") (pintype "passive"))
      (node (ref "S1") (pin "C") (pinfunction "NO_C") (pintype "passive"))
      (node (ref "S1") (pin "D") (pinfunction "NO_D") (pintype "passive"))
      (node (ref "U5") (pin "30") (pinfunction "~{RESET}_30") (pintype "input"))
    )
    (net (code "72") (name "/RXD") (class "Default")
      (node (ref "LED2") (pin "C") (pinfunction "C_C") (pintype "passive"))
      (node (ref "R14") (pin "1") (pinfunction "1_1") (pintype "passive"))
      (node (ref "U1") (pin "3") (pinfunction "RXD_3") (pintype "input"))
    )
    (net (code "73") (name "/SCK") (class "Default")
      (node (ref "H2") (pin "31") (pinfunction "31_31") (pintype "passive"))
      (node (ref "H4") (pin "03") (pinfunction "03_03") (pintype "passive"))
      (node (ref "U5") (pin "20") (pinfunction "PB1/SCK/PCINT1_20") (pintype "bidirectional"))
    )
    (net (code "74") (name "/SS") (class "Default")
      (node (ref "H2") (pin "32") (pinfunction "32_32") (pintype "passive"))
      (node (ref "U5") (pin "19") (pinfunction "PB0/~{SS}/PCINT0_19") (pintype "bidirectional"))
    )
    (net (code "75") (name "/TXD") (class "Default")
      (node (ref "LED1") (pin "C") (pinfunction "C_C") (pintype "passive"))
      (node (ref "R13") (pin "1") (pinfunction "1_1") (pintype "passive"))
      (node (ref "U1") (pin "2") (pinfunction "TXD_2") (pintype "output"))
    )
    (net (code "76") (name "/USB_N") (class "Default")
      (node (ref "R2") (pin "2") (pinfunction "2_2") (pintype "passive"))
      (node (ref "U1") (pin "6") (pinfunction "UD-_6") (pintype "bidirectional"))
      (node (ref "U4") (pin "1") (pinfunction "I/O_1") (pintype "passive"))
    )
    (net (code "77") (name "/USB_P") (class "Default")
      (node (ref "R3") (pin "2") (pinfunction "2_2") (pintype "passive"))
      (node (ref "U1") (pin "5") (pinfunction "UD+_5") (pintype "bidirectional"))
      (node (ref "U4") (pin "3") (pinfunction "I/O_3") (pintype "passive"))
    )
    (net (code "78") (name "/XTAL1") (class "Default")
      (node (ref "C16") (pin "2") (pinfunction "2_2") (pintype "passive"))
      (node (ref "R12") (pin "1") (pinfunction "1_1") (pintype "passive"))
      (node (ref "U5") (pin "34") (pinfunction "XTAL1_34") (pintype "input"))
      (node (ref "X2") (pin "3") (pinfunction "3_3") (pintype "passive"))
    )
    (net (code "79") (name "/XTAL2") (class "Default")
      (node (ref "C15") (pin "2") (pinfunction "2_2") (pintype "passive"))
      (node (ref "R12") (pin "2") (pinfunction "2_2") (pintype "passive"))
      (node (ref "U5") (pin "33") (pinfunction "XTAL2_33") (pintype "output"))
      (node (ref "X2") (pin "1") (pinfunction "1_1") (pintype "passive"))
    )
    (net (code "80") (name "3.3V") (class "Default")
      (node (ref "C8") (pin "2") (pinfunction "2_2") (pintype "passive"))
      (node (ref "C9") (pin "2") (pinfunction "2_2") (pintype "passive"))
      (node (ref "H1") (pin "07") (pinfunction "07_07") (pintype "power_in"))
      (node (ref "H1") (pin "08") (pinfunction "08_08") (pintype "power_in"))
      (node (ref "U3") (pin "2") (pinfunction "VOUT_2") (pintype "power_in"))
    )
    (net (code "81") (name "GND") (class "Default")
      (node (ref "C1") (pin "1") (pinfunction "1_1") (pintype "passive"))
      (node (ref "C10") (pin "2") (pinfunction "2_2") (pintype "passive"))
      (node (ref "C11") (pin "1") (pinfunction "1_1") (pintype "passive"))
      (node (ref "C12") (pin "1") (pinfunction "1_1") (pintype "passive"))
      (node (ref "C13") (pin "1") (pinfunction "1_1") (pintype "passive"))
      (node (ref "C14") (pin "1") (pinfunction "1_1") (pintype "passive"))
      (node (ref "C15") (pin "1") (pinfunction "1_1") (pintype "passive"))
      (node (ref "C16") (pin "1") (pinfunction "1_1") (pintype "passive"))
      (node (ref "C3") (pin "1") (pinfunction "1_1") (pintype "passive"))
      (node (ref "C4") (pin "1") (pinfunction "1_1") (pintype "passive"))
      (node (ref "C5") (pin "1") (pinfunction "1_1") (pintype "passive"))
      (node (ref "C6") (pin "1") (pinfunction "1_1") (pintype "passive"))
      (node (ref "C7") (pin "1") (pinfunction "1_1") (pintype "passive"))
      (node (ref "C8") (pin "1") (pinfunction "1_1") (pintype "passive"))
      (node (ref "C9") (pin "1") (pinfunction "1_1") (pintype "passive"))
      (node (ref "H1") (pin "03") (pinfunction "03_03") (pintype "power_in"))
      (node (ref "H1") (pin "04") (pinfunction "04_04") (pintype "power_in"))
      (node (ref "H4") (pin "06") (pinfunction "06_06") (pintype "passive"))
      (node (ref "LED3") (pin "C") (pinfunction "C_C") (pintype "passive"))
      (node (ref "LED4") (pin "C") (pinfunction "C_C") (pintype "passive"))
      (node (ref "R1") (pin "2") (pinfunction "2_2") (pintype "passive"))
      (node (ref "S1") (pin "A") (pinfunction "COM_A") (pintype "passive"))
      (node (ref "S1") (pin "B") (pinfunction "COM_B") (pintype "passive"))
      (node (ref "U1") (pin "1") (pinfunction "GND_1") (pintype "power_in"))
      (node (ref "U2") (pin "1") (pinfunction "ADJ/GND_1") (pintype "power_in"))
      (node (ref "U3") (pin "1") (pinfunction "ADJ/GND_1") (pintype "power_in"))
      (node (ref "U4") (pin "2") (pinfunction "VN_2") (pintype "power_in"))
      (node (ref "U5") (pin "11") (pinfunction "GND_11") (pintype "power_in"))
      (node (ref "U5") (pin "32") (pinfunction "GND_32") (pintype "power_in"))
      (node (ref "U5") (pin "62") (pinfunction "GND_62") (pintype "power_in"))
      (node (ref "U5") (pin "81") (pinfunction "GND_81") (pintype "power_in"))
      (node (ref "U5") (pin "99") (pinfunction "GND_99") (pintype "power_in"))
      (node (ref "USB1") (pin "5") (pinfunction "GND_5") (pintype "passive"))
      (node (ref "USB1") (pin "S1") (pinfunction "SHIELD_S1") (pintype "passive"))
      (node (ref "USB1") (pin "S2") (pinfunction "SHIELD_S2") (pintype "passive"))
      (node (ref "USB1") (pin "S3") (pinfunction "SHIELD_S3") (pintype "passive"))
      (node (ref "USB1") (pin "S4") (pinfunction "SHIELD_S4") (pintype "passive"))
      (node (ref "USB1") (pin "S5") (pinfunction "SHIELD_S5") (pintype "passive"))
      (node (ref "USB1") (pin "S6") (pinfunction "SHIELD_S6") (pintype "passive"))
      (node (ref "X1") (pin "2") (pinfunction "GND_2") (pintype "power_in"))
      (node (ref "X1") (pin "4") (pinfunction "GND_4") (pintype "power_in"))
      (node (ref "X2") (pin "2") (pinfunction "GND_2") (pintype "power_in"))
      (node (ref "X2") (pin "4") (pinfunction "GND_4") (pintype "power_in"))
    )
    (net (code "82") (name "Net-(LED1-PadA)") (class "Default")
      (node (ref "LED1") (pin "A") (pinfunction "A_A") (pintype "passive"))
      (node (ref "R5") (pin "2") (pinfunction "2_2") (pintype "passive"))
    )
    (net (code "83") (name "Net-(LED2-PadA)") (class "Default")
      (node (ref "LED2") (pin "A") (pinfunction "A_A") (pintype "passive"))
      (node (ref "R6") (pin "2") (pinfunction "2_2") (pintype "passive"))
    )
    (net (code "84") (name "Net-(LED3-PadA)") (class "Default")
      (node (ref "LED3") (pin "A") (pinfunction "A_A") (pintype "passive"))
      (node (ref "R7") (pin "2") (pinfunction "2_2") (pintype "passive"))
    )
    (net (code "85") (name "Net-(LED4-PadA)") (class "Default")
      (node (ref "LED4") (pin "A") (pinfunction "A_A") (pintype "passive"))
      (node (ref "R8") (pin "2") (pinfunction "2_2") (pintype "passive"))
    )
    (net (code "86") (name "Net-(U1-DTR#)") (class "Default")
      (node (ref "C2") (pin "1") (pinfunction "1_1") (pintype "passive"))
      (node (ref "R1") (pin "1") (pinfunction "1_1") (pintype "passive"))
      (node (ref "U1") (pin "13") (pinfunction "DTR#_13") (pintype "output"))
    )
    (net (code "87") (name "Net-(U1-V3)") (class "Default")
      (node (ref "C1") (pin "2") (pinfunction "2_2") (pintype "passive"))
      (node (ref "U1") (pin "4") (pinfunction "V3_4") (pintype "power_in"))
    )
    (net (code "88") (name "Net-(U1-XI)") (class "Default")
      (node (ref "C3") (pin "2") (pinfunction "2_2") (pintype "passive"))
      (node (ref "R4") (pin "2") (pinfunction "2_2") (pintype "passive"))
      (node (ref "U1") (pin "7") (pinfunction "XI_7") (pintype "input"))
      (node (ref "X1") (pin "1") (pinfunction "1_1") (pintype "passive"))
    )
    (net (code "89") (name "Net-(U1-XO)") (class "Default")
      (node (ref "C4") (pin "2") (pinfunction "2_2") (pintype "passive"))
      (node (ref "R4") (pin "1") (pinfunction "1_1") (pintype "passive"))
      (node (ref "U1") (pin "8") (pinfunction "XO_8") (pintype "output"))
      (node (ref "X1") (pin "3") (pinfunction "3_3") (pintype "passive"))
    )
    (net (code "90") (name "Net-(U2-VIN)") (class "Default")
      (node (ref "C5") (pin "2") (pinfunction "2_2") (pintype "passive"))
      (node (ref "D2") (pin "C") (pinfunction "C_C") (pintype "passive"))
      (node (ref "U2") (pin "3") (pinfunction "VIN_3") (pintype "power_in"))
    )
    (net (code "91") (name "Net-(USB1-D+)") (class "Default")
      (node (ref "R3") (pin "1") (pinfunction "1_1") (pintype "passive"))
      (node (ref "USB1") (pin "3") (pinfunction "D+_3") (pintype "passive"))
    )
    (net (code "92") (name "Net-(USB1-D-)") (class "Default")
      (node (ref "R2") (pin "1") (pinfunction "1_1") (pintype "passive"))
      (node (ref "USB1") (pin "2") (pinfunction "D-_2") (pintype "passive"))
    )
    (net (code "93") (name "Net-(USB1-VUSB)") (class "Default")
      (node (ref "F1") (pin "1") (pinfunction "1_1") (pintype "passive"))
      (node (ref "USB1") (pin "1") (pinfunction "VUSB_1") (pintype "power_in"))
    )
    (net (code "94") (name "VIN") (class "Default")
      (node (ref "D2") (pin "A") (pinfunction "A_A") (pintype "passive"))
      (node (ref "H1") (pin "01") (pinfunction "01_01") (pintype "power_in"))
      (node (ref "H1") (pin "02") (pinfunction "02_02") (pintype "power_in"))
    )
    (net (code "95") (name "unconnected-(U1-CTS#-Pad9)") (class "Default")
      (node (ref "U1") (pin "9") (pinfunction "CTS#_9") (pintype "input+no_connect"))
    )
    (net (code "96") (name "unconnected-(U1-DCD#-Pad12)") (class "Default")
      (node (ref "U1") (pin "12") (pinfunction "DCD#_12") (pintype "input+no_connect"))
    )
    (net (code "97") (name "unconnected-(U1-DSR#-Pad10)") (class "Default")
      (node (ref "U1") (pin "10") (pinfunction "DSR#_10") (pintype "input+no_connect"))
    )
    (net (code "98") (name "unconnected-(U1-R232-Pad15)") (class "Default")
      (node (ref "U1") (pin "15") (pinfunction "R232_15") (pintype "input+no_connect"))
    )
    (net (code "99") (name "unconnected-(U1-RI#-Pad11)") (class "Default")
      (node (ref "U1") (pin "11") (pinfunction "RI#_11") (pintype "input+no_connect"))
    )
    (net (code "100") (name "unconnected-(U1-RTS#-Pad14)") (class "Default")
      (node (ref "U1") (pin "14") (pinfunction "RTS#_14") (pintype "output+no_connect"))
    )
    (net (code "101") (name "unconnected-(U4-I{slash}O-Pad4)") (class "Default")
      (node (ref "U4") (pin "4") (pinfunction "I/O_4") (pintype "passive+no_connect"))
    )
    (net (code "102") (name "unconnected-(U4-I{slash}O-Pad6)") (class "Default")
      (node (ref "U4") (pin "6") (pinfunction "I/O_6") (pintype "passive+no_connect"))
    )
    (net (code "103") (name "unconnected-(U5-PD4{slash}ICP1-Pad47)") (class "Default")
      (node (ref "U5") (pin "47") (pinfunction "PD4/ICP1_47") (pintype "bidirectional+no_connect"))
    )
    (net (code "104") (name "unconnected-(U5-PD5{slash}XCK1-Pad48)") (class "Default")
      (node (ref "U5") (pin "48") (pinfunction "PD5/XCK1_48") (pintype "bidirectional+no_connect"))
    )
    (net (code "105") (name "unconnected-(U5-PD6{slash}T1-Pad49)") (class "Default")
      (node (ref "U5") (pin "49") (pinfunction "PD6/T1_49") (pintype "bidirectional+no_connect"))
    )
    (net (code "106") (name "unconnected-(U5-PE2{slash}XCK0{slash}AIN0-Pad4)") (class "Default")
      (node (ref "U5") (pin "4") (pinfunction "PE2/XCK0/AIN0_4") (pintype "bidirectional+no_connect"))
    )
    (net (code "107") (name "unconnected-(U5-PE6{slash}T3{slash}INT6-Pad8)") (class "Default")
      (node (ref "U5") (pin "8") (pinfunction "PE6/T3/INT6_8") (pintype "bidirectional+no_connect"))
    )
    (net (code "108") (name "unconnected-(U5-PE7{slash}CLKO{slash}ICP3{slash}INT7-Pad9)") (class "Default")
      (node (ref "U5") (pin "9") (pinfunction "PE7/CLKO/ICP3/INT7_9") (pintype "bidirectional+no_connect"))
    )
    (net (code "109") (name "unconnected-(U5-PG3{slash}TOSC2-Pad28)") (class "Default")
      (node (ref "U5") (pin "28") (pinfunction "PG3/TOSC2_28") (pintype "bidirectional+no_connect"))
    )
    (net (code "110") (name "unconnected-(U5-PG4{slash}TOSC1-Pad29)") (class "Default")
      (node (ref "U5") (pin "29") (pinfunction "PG4/TOSC1_29") (pintype "bidirectional+no_connect"))
    )
    (net (code "111") (name "unconnected-(U5-PH2{slash}XCK2-Pad14)") (class "Default")
      (node (ref "U5") (pin "14") (pinfunction "PH2/XCK2_14") (pintype "bidirectional+no_connect"))
    )
    (net (code "112") (name "unconnected-(U5-PH7{slash}T4-Pad27)") (class "Default")
      (node (ref "U5") (pin "27") (pinfunction "PH7/T4_27") (pintype "bidirectional+no_connect"))
    )
    (net (code "113") (name "unconnected-(U5-PJ2{slash}XCK3{slash}PCINT11-Pad65)") (class "Default")
      (node (ref "U5") (pin "65") (pinfunction "PJ2/XCK3/PCINT11_65") (pintype "bidirectional+no_connect"))
    )
    (net (code "114") (name "unconnected-(U5-PJ3{slash}PCINT12-Pad66)") (class "Default")
      (node (ref "U5") (pin "66") (pinfunction "PJ3/PCINT12_66") (pintype "bidirectional+no_connect"))
    )
    (net (code "115") (name "unconnected-(U5-PJ4{slash}PCINT13-Pad67)") (class "Default")
      (node (ref "U5") (pin "67") (pinfunction "PJ4/PCINT13_67") (pintype "bidirectional+no_connect"))
    )
    (net (code "116") (name "unconnected-(U5-PJ5{slash}PCINT14-Pad68)") (class "Default")
      (node (ref "U5") (pin "68") (pinfunction "PJ5/PCINT14_68") (pintype "bidirectional+no_connect"))
    )
    (net (code "117") (name "unconnected-(U5-PJ6{slash}PCINT15-Pad69)") (class "Default")
      (node (ref "U5") (pin "69") (pinfunction "PJ6/PCINT15_69") (pintype "bidirectional+no_connect"))
    )
    (net (code "118") (name "unconnected-(U5-PJ7-Pad79)") (class "Default")
      (node (ref "U5") (pin "79") (pinfunction "PJ7_79") (pintype "bidirectional+no_connect"))
    )
    (net (code "119") (name "unconnected-(USB1-ID-Pad4)") (class "Default")
      (node (ref "USB1") (pin "4") (pinfunction "ID_4") (pintype "passive+no_connect"))
    )
  )
)
